# ISRelayV12.net
KiCad netlist of a schematic drawn in EAGLE
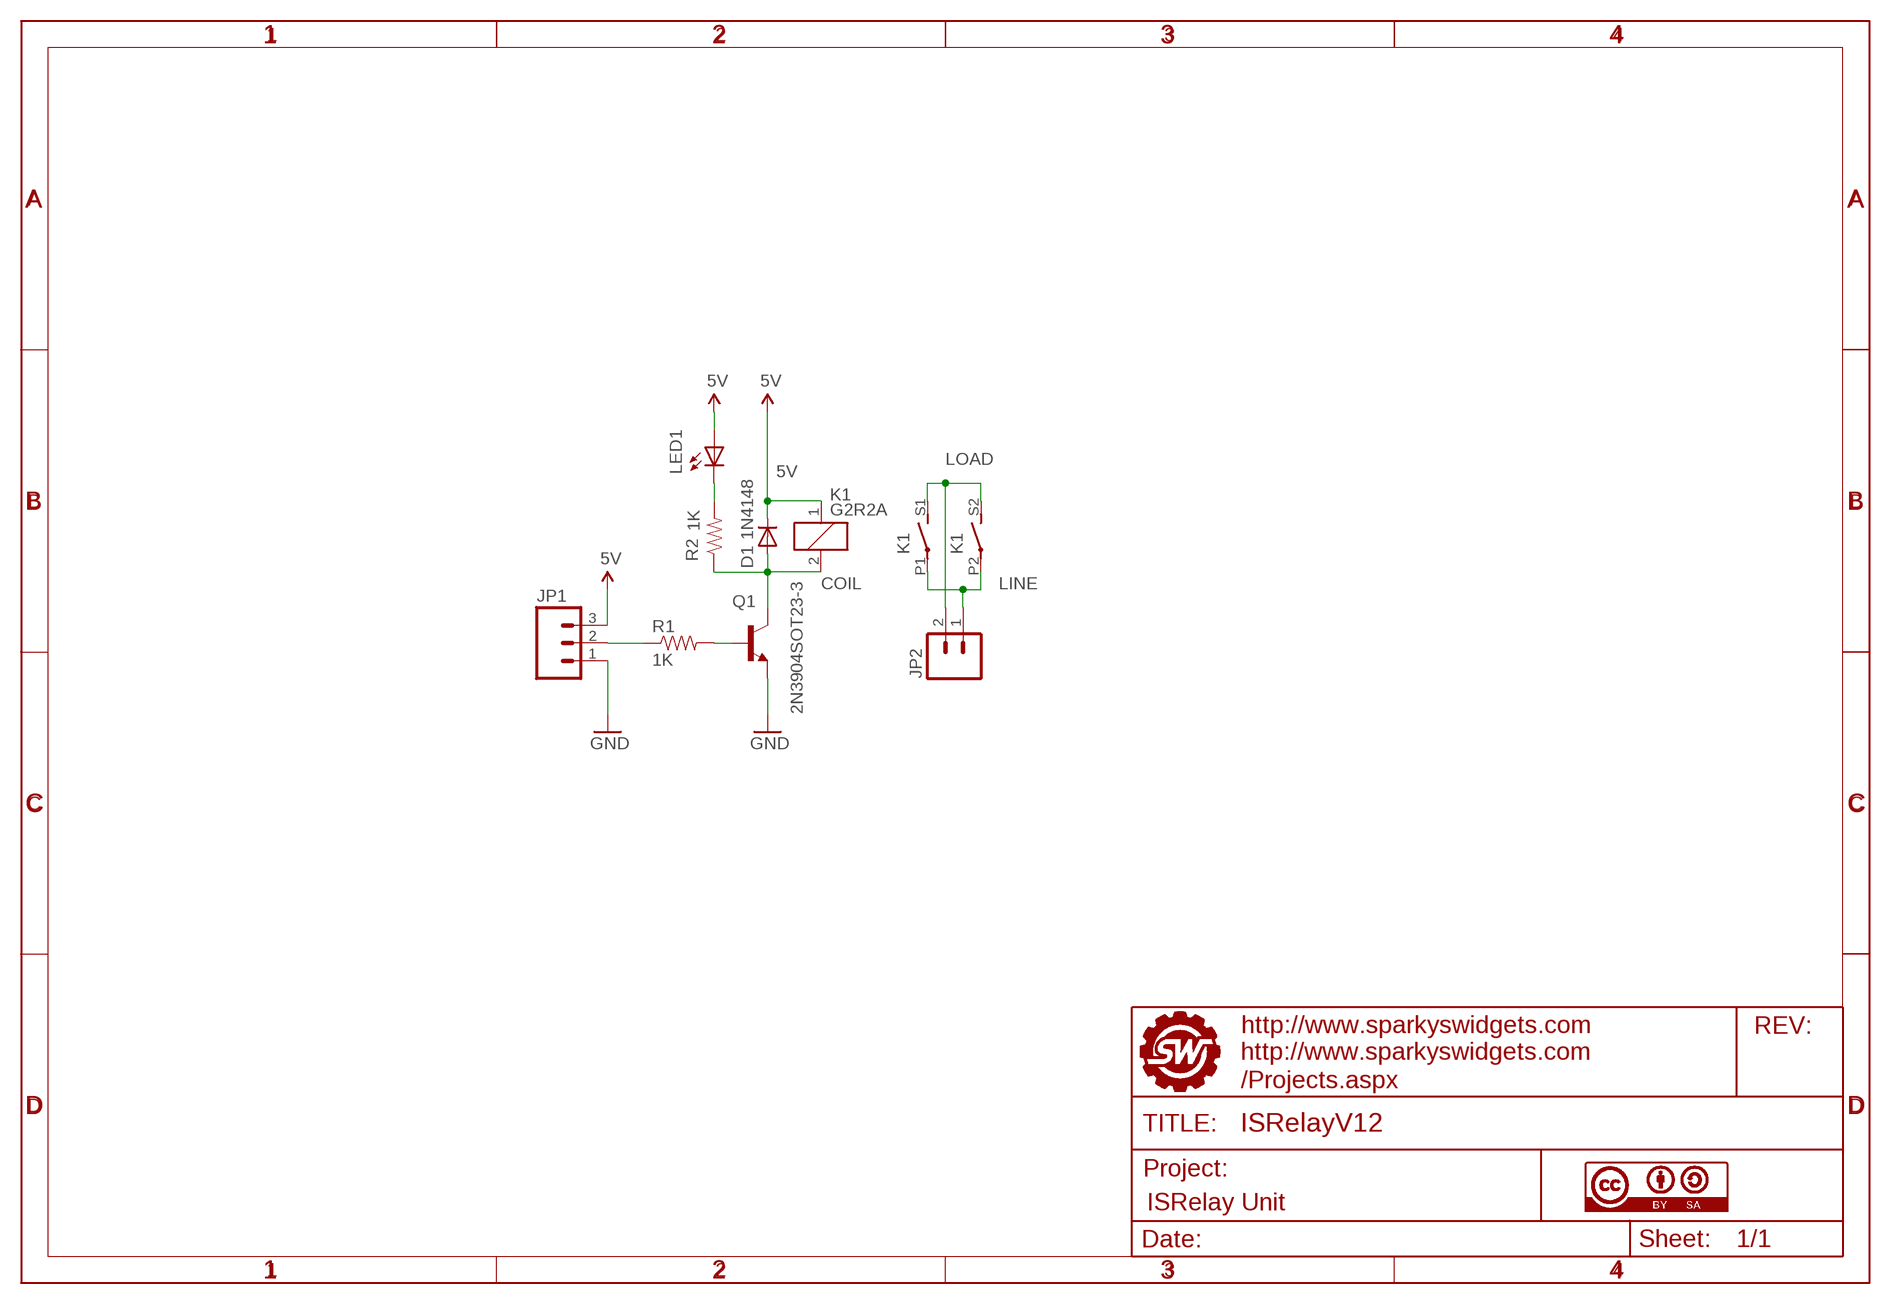
[diagram p0: schematic, sheet 1]

(export (version "E")
  (design (tool "Eeschema 10.0.6"))
  (components
    (comp (ref "D1")
      (value "1N4148")
      (footprint "eagle-import:SOD123")
      (libsource (lib "eagle-import") (part "MBR0520LT"))
    )
    (comp (ref "JP1")
      (value "M03SCREW")
      (footprint "eagle-import:SCREWTERMINAL-3.5MM-3")
      (libsource (lib "eagle-import") (part "M03SCREW"))
    )
    (comp (ref "JP2")
      (value "M025MM")
      (footprint "eagle-import:SCREWTERMINAL-5MM-2")
      (libsource (lib "eagle-import") (part "M025MM"))
    )
    (comp (ref "K1")
      (value "G2R2A")
      (footprint "eagle-import:G2R2A")
      (fields (field (name "MPN") "G2R-2A-DC24"))
      (libsource (lib "eagle-import") (part "G2R2A"))
    )
    (comp (ref "LED1")
      (value "LEDCHIP-LED0805")
      (footprint "eagle-import:CHIP-LED0805")
      (libsource (lib "eagle-import") (part "LEDCHIP-LED0805"))
    )
    (comp (ref "Q1")
      (value "2N3904SOT23-3")
      (footprint "eagle-import:SOT-23")
      (libsource (lib "eagle-import") (part "2N3904SOT23-3"))
    )
    (comp (ref "R1")
      (value "1K")
      (footprint "eagle-import:0805")
      (libsource (lib "eagle-import") (part "RESISTOR0805-RES"))
    )
    (comp (ref "R2")
      (value "1K")
      (footprint "eagle-import:0805")
      (libsource (lib "eagle-import") (part "RESISTOR0805-RES"))
    )
    (comp (ref "U$9")
      (value "CC-BY-SA")
      (footprint "eagle-import:CC-BY-SA")
      (libsource (lib "eagle-import") (part "CC-BY-SA"))
    )
    (comp (ref "U$11")
      (value "FRAME_SW_LOGO_CC_BY_SA")
      (footprint "eagle-import:SWPCBLOGOWITHINFO")
      (libsource (lib "eagle-import") (part "FRAME_SW_LOGO_CC_BY_SA"))
    )
  )
  (nets
    (net (code "1") (name "/COIL") (class "Default")
      (node (ref "D1") (pin "A") (pinfunction "A_A") (pintype "passive"))
      (node (ref "K1") (pin "2") (pinfunction "2_2") (pintype "passive"))
      (node (ref "Q1") (pin "1") (pinfunction "C_1") (pintype "passive"))
      (node (ref "R2") (pin "1") (pinfunction "1_1") (pintype "passive"))
    )
    (net (code "2") (name "/LINE") (class "Default")
      (node (ref "JP2") (pin "1") (pinfunction "1_1") (pintype "passive"))
      (node (ref "K1") (pin "P1") (pinfunction "P_P1") (pintype "passive"))
      (node (ref "K1") (pin "P2") (pinfunction "P_P2") (pintype "passive"))
    )
    (net (code "3") (name "/LOAD") (class "Default")
      (node (ref "JP2") (pin "2") (pinfunction "2_2") (pintype "passive"))
      (node (ref "K1") (pin "S1") (pinfunction "S_S1") (pintype "passive"))
      (node (ref "K1") (pin "S2") (pinfunction "S_S2") (pintype "passive"))
    )
    (net (code "4") (name "5V") (class "Default")
      (node (ref "D1") (pin "C") (pinfunction "C_C") (pintype "passive"))
      (node (ref "JP1") (pin "3") (pinfunction "3_3") (pintype "passive"))
      (node (ref "K1") (pin "1") (pinfunction "1_1") (pintype "passive"))
      (node (ref "LED1") (pin "A") (pinfunction "A_A") (pintype "passive"))
    )
    (net (code "5") (name "GND") (class "Default")
      (node (ref "JP1") (pin "1") (pinfunction "1_1") (pintype "passive"))
      (node (ref "Q1") (pin "2") (pinfunction "E_2") (pintype "passive"))
    )
    (net (code "6") (name "Net-(JP1-Pad2)") (class "Default")
      (node (ref "JP1") (pin "2") (pinfunction "2_2") (pintype "passive"))
      (node (ref "R1") (pin "1") (pinfunction "1_1") (pintype "passive"))
    )
    (net (code "7") (name "Net-(LED1-PadC)") (class "Default")
      (node (ref "LED1") (pin "C") (pinfunction "C_C") (pintype "passive"))
      (node (ref "R2") (pin "2") (pinfunction "2_2") (pintype "passive"))
    )
    (net (code "8") (name "Net-(Q1-B)") (class "Default")
      (node (ref "Q1") (pin "3") (pinfunction "B_3") (pintype "passive"))
      (node (ref "R1") (pin "2") (pinfunction "2_2") (pintype "passive"))
    )
  )
)
